# tlv117_5_3_3.net
KiCad netlist of a schematic drawn in Altium Designer
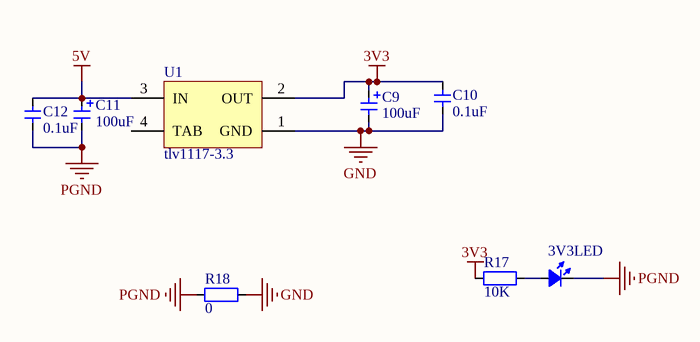
[diagram p0: tlv117_5_3.3.SchDoc]

(export (version "E")
  (design (tool "Eeschema 10.0.6"))
  (components
    (comp (ref "3V3LED")
      (value "LED_0805")
      (footprint "LED_0805_BLUE")
      (description "LED")
      (libsource (lib "SCH_Active") (part "LED_0603"))
    )
    (comp (ref "C9")
      (value "100uF")
      (footprint "CAP-TAN-6032/CAPC")
      (description "Capacitor")
      (fields (field (name "Comment") "Cap_Tan_0805"))
      (libsource (lib "Integrated_Library") (part "Cap_Tan_0805"))
    )
    (comp (ref "C10")
      (value "0.1uF")
      (footprint "CAP_0603")
      (description "Capacitor")
      (fields (field (name "Comment") "Cap_0603"))
      (libsource (lib "Integrated_Library") (part "Cap_0603"))
    )
    (comp (ref "C11")
      (value "100uF")
      (footprint "CAP-TAN-6032/CAPC")
      (description "Capacitor")
      (fields (field (name "Comment") "Cap_Tan_0805"))
      (libsource (lib "Integrated_Library") (part "Cap_Tan_0805"))
    )
    (comp (ref "C12")
      (value "0.1uF")
      (footprint "CAP_0603")
      (description "Capacitor")
      (fields (field (name "Comment") "Cap_0603"))
      (libsource (lib "Integrated_Library") (part "Cap_0603"))
    )
    (comp (ref "R17")
      (value "10K")
      (footprint "RES_0603")
      (description "Resistor")
      (fields (field (name "Comment") "Res_0603"))
      (libsource (lib "Integrated_Library") (part "Res_0603"))
    )
    (comp (ref "R18")
      (value "0")
      (footprint "RES_0603")
      (description "Resistor")
      (fields (field (name "Comment") "Res_0603"))
      (libsource (lib "Integrated_Library") (part "Res_0603"))
    )
    (comp (ref "U1")
      (value "tlv1117-3.3")
      (footprint "SOT223-3")
      (description "800mA Low-Dropout Linear Regulator")
      (fields
        (field (name "PARTNUMBER") "LM1117IMP-5.0")
        (field (name "MANUFACTURER") "National Semiconductor")
        (field (name "PUBLISHER") "Altium Limited")
      )
      (libsource (lib "K60-mainboard-v3.1") (part "LM1117IMP-5.0"))
    )
  )
  (nets
    (net (code "1") (name "3V3") (class "Default")
      (node (ref "C10") (pin "2") (pinfunction "2_2") (pintype "passive"))
      (node (ref "C9") (pin "1") (pinfunction "1_1") (pintype "passive"))
      (node (ref "R17") (pin "1") (pinfunction "1_1") (pintype "passive"))
      (node (ref "U1") (pin "2") (pinfunction "OUT_2") (pintype "power_in"))
    )
    (net (code "2") (name "5V") (class "Default")
      (node (ref "C11") (pin "1") (pinfunction "1_1") (pintype "passive"))
      (node (ref "C12") (pin "2") (pinfunction "2_2") (pintype "passive"))
      (node (ref "U1") (pin "3") (pinfunction "IN_3") (pintype "power_in"))
    )
    (net (code "3") (name "GND") (class "Default")
      (node (ref "C10") (pin "1") (pinfunction "1_1") (pintype "passive"))
      (node (ref "C9") (pin "2") (pinfunction "2_2") (pintype "passive"))
      (node (ref "R18") (pin "2") (pinfunction "2_2") (pintype "passive"))
      (node (ref "U1") (pin "1") (pinfunction "GND_1") (pintype "power_in"))
    )
    (net (code "4") (name "Net-(3V3LED-A)") (class "Default")
      (node (ref "3V3LED") (pin "1") (pinfunction "A_1") (pintype "passive"))
      (node (ref "R17") (pin "2") (pinfunction "2_2") (pintype "passive"))
    )
    (net (code "5") (name "PGND") (class "Default")
      (node (ref "3V3LED") (pin "2") (pinfunction "K_2") (pintype "passive"))
      (node (ref "C11") (pin "2") (pinfunction "2_2") (pintype "passive"))
      (node (ref "C12") (pin "1") (pinfunction "1_1") (pintype "passive"))
      (node (ref "R18") (pin "1") (pinfunction "1_1") (pintype "passive"))
    )
    (net (code "6") (name "unconnected-(U1-TAB-Pad4)") (class "Default")
      (node (ref "U1") (pin "4") (pinfunction "TAB_4") (pintype "power_in"))
    )
  )
)
